# USB_Serial.net
KiCad netlist of a schematic drawn in EAGLE
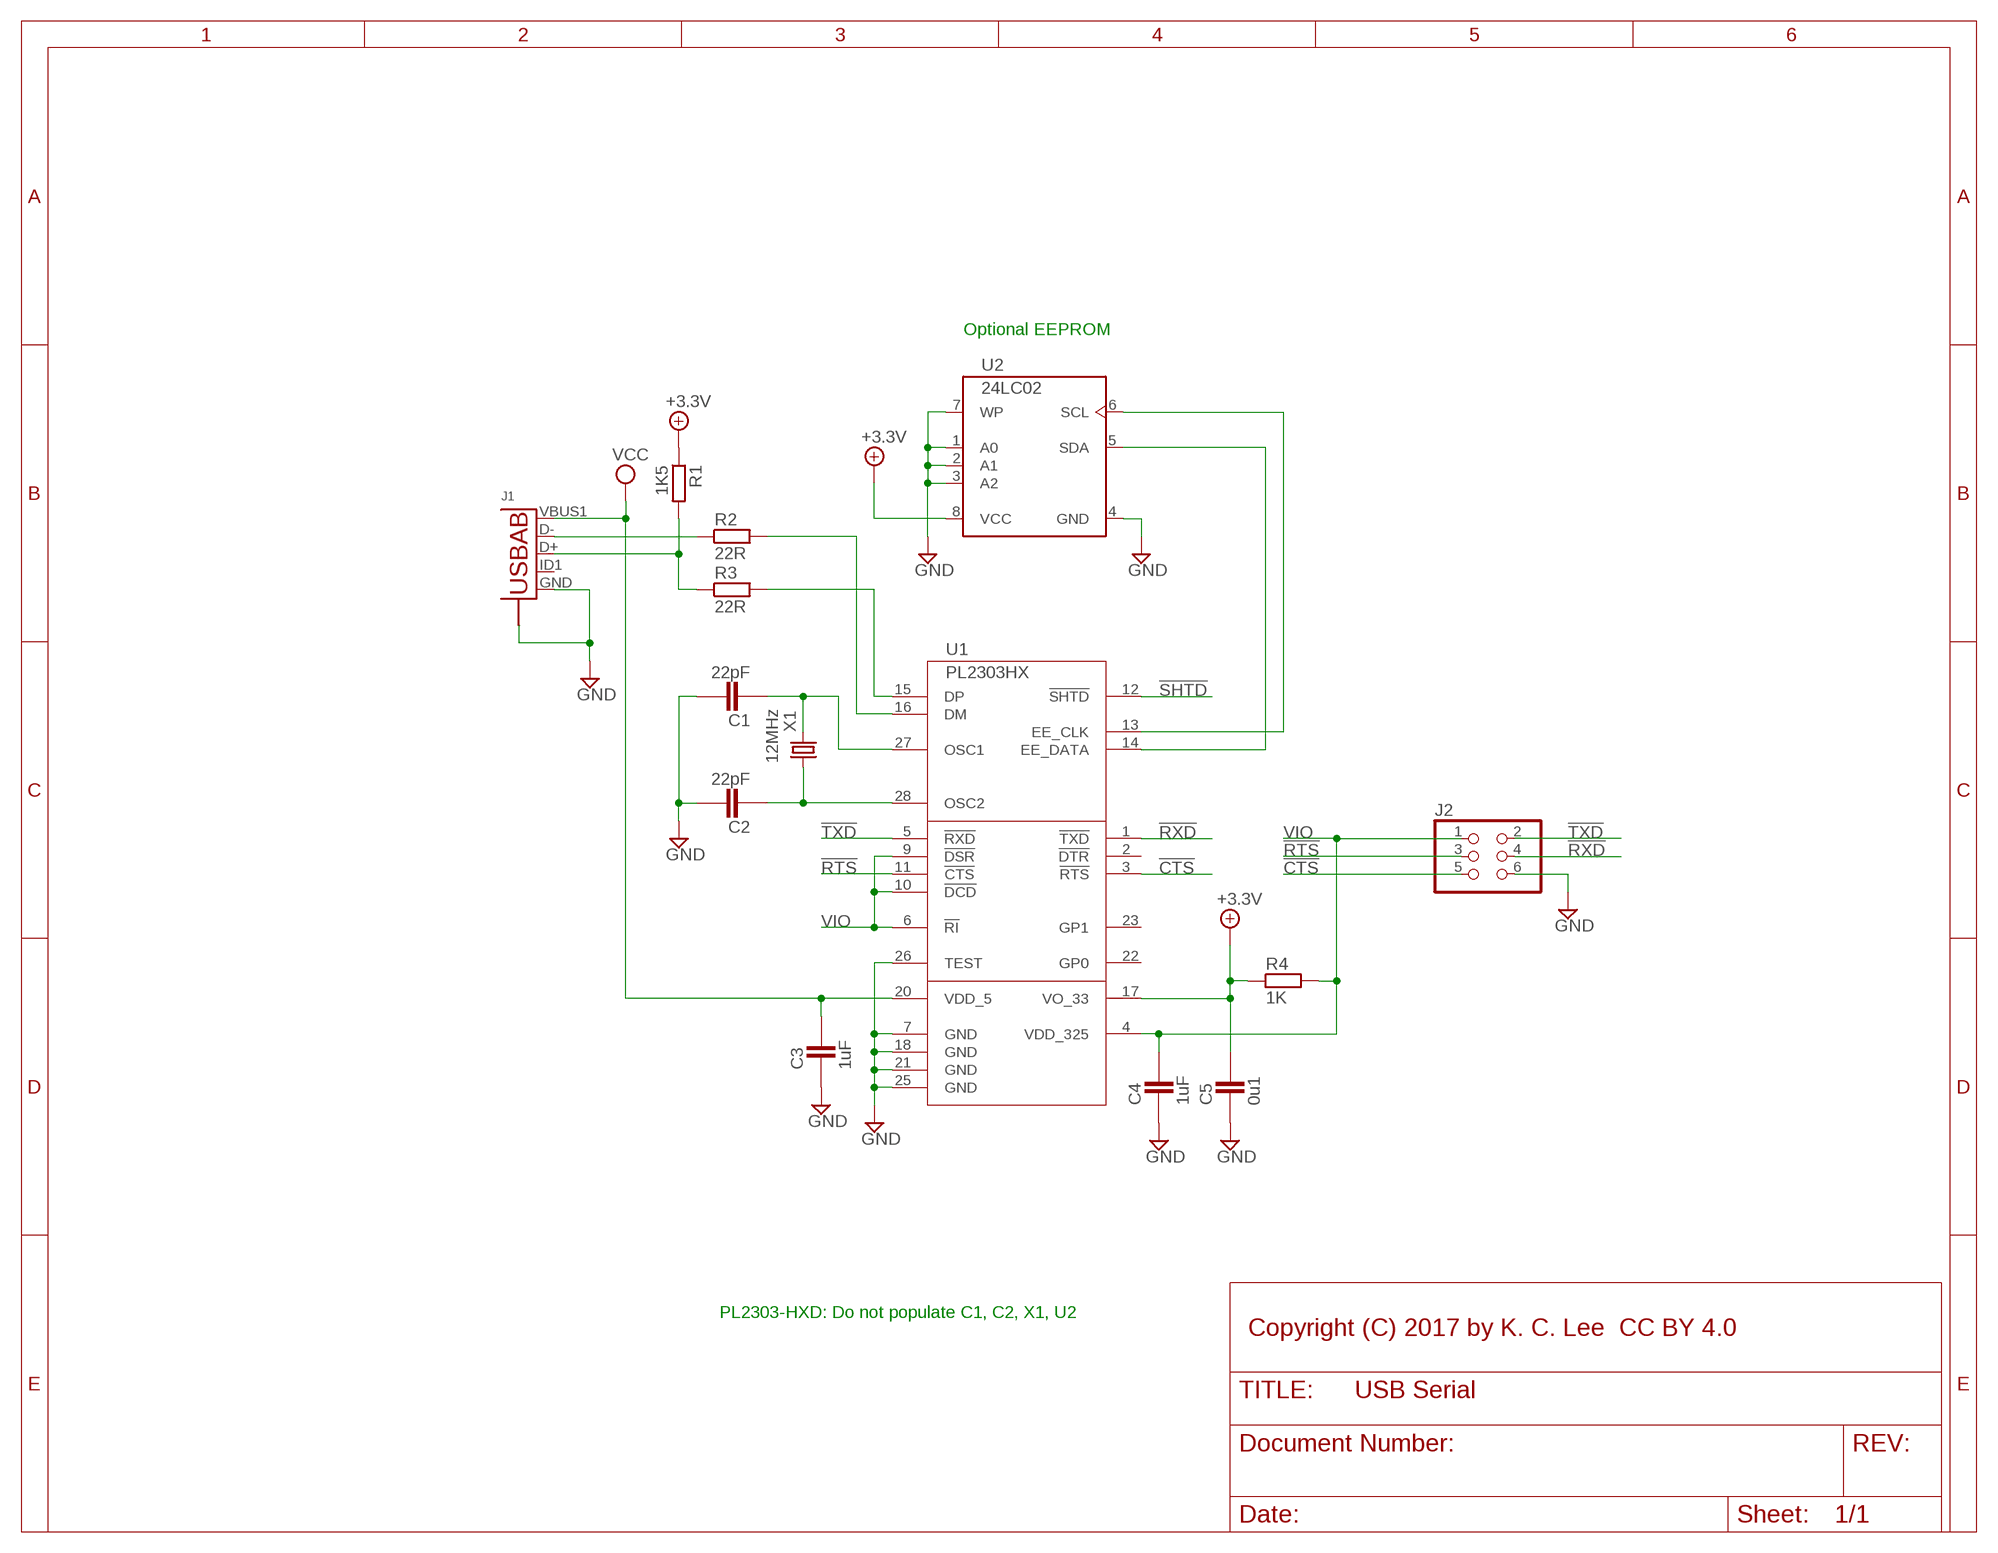
[diagram p0: schematic, sheet 1]

(export (version "E")
  (design (tool "Eeschema 10.0.6"))
  (components
    (comp (ref "C1")
      (value "22pF")
      (footprint "eagle-import:CAPC1608X92N")
      (fields (field (name "PARTNO") "22PF 0603"))
      (libsource (lib "eagle-import") (part "CAPACITOR_0603"))
    )
    (comp (ref "C2")
      (value "22pF")
      (footprint "eagle-import:CAPC1608X92N")
      (fields (field (name "PARTNO") "22PF 0603"))
      (libsource (lib "eagle-import") (part "CAPACITOR_0603"))
    )
    (comp (ref "C3")
      (value "1uF")
      (footprint "eagle-import:CAPC1608X92N")
      (fields (field (name "PARTNO") "1UF X7R 0603"))
      (libsource (lib "eagle-import") (part "CAPACITOR_0603"))
    )
    (comp (ref "C4")
      (value "1uF")
      (footprint "eagle-import:CAPC1608X92N")
      (fields (field (name "PARTNO") "1UF X7R 0603"))
      (libsource (lib "eagle-import") (part "CAPACITOR_0603"))
    )
    (comp (ref "C5")
      (value "0u1")
      (footprint "eagle-import:CAPC1608X92N")
      (fields (field (name "PARTNO") "0U1 X7R 0603"))
      (libsource (lib "eagle-import") (part "CAPACITOR_0603"))
    )
    (comp (ref "J1")
      (value "USB-ABBG-ORG")
      (footprint "eagle-import:USB-AB-MICRO-SMD_V03_SMT")
      (fields (field (name "PARTNO") "SMT MICRO USB FEMALE"))
      (libsource (lib "eagle-import") (part "USB-ABBG-ORG"))
    )
    (comp (ref "J2")
      (value "PINHD-2X3_2.00")
      (footprint "eagle-import:2X03M_TH")
      (fields (field (name "PARTNO") "3X2 HEADER 2MM THROUGH HOLE"))
      (libsource (lib "eagle-import") (part "PINHD-2X3_2.00"))
    )
    (comp (ref "R1")
      (value "1K5")
      (footprint "eagle-import:RESC1608X55N")
      (fields (field (name "PARTNO") "1K5 0603"))
      (libsource (lib "eagle-import") (part "RESISTOR_0603"))
    )
    (comp (ref "R2")
      (value "22R")
      (footprint "eagle-import:RESC1608X55N")
      (fields (field (name "PARTNO") "22R 0603"))
      (libsource (lib "eagle-import") (part "RESISTOR_0603"))
    )
    (comp (ref "R3")
      (value "22R")
      (footprint "eagle-import:RESC1608X55N")
      (fields (field (name "PARTNO") "22R 0603"))
      (libsource (lib "eagle-import") (part "RESISTOR_0603"))
    )
    (comp (ref "R4")
      (value "1K")
      (footprint "eagle-import:RESC1608X55N")
      (fields (field (name "PARTNO") "1K 0603"))
      (libsource (lib "eagle-import") (part "RESISTOR_0603"))
    )
    (comp (ref "U1")
      (value "PL2303HX")
      (footprint "eagle-import:SSOP28DB")
      (fields (field (name "PARTNO") "PL-2303HXD SSOP"))
      (libsource (lib "eagle-import") (part "PL2303HXASSOP"))
    )
    (comp (ref "U2")
      (value "24LC02")
      (footprint "eagle-import:TSSOP8")
      (libsource (lib "eagle-import") (part "24ST"))
    )
    (comp (ref "X1")
      (value "12MHz")
      (footprint "eagle-import:TC26H")
      (fields (field (name "PARTNO") "12MHZ TC26"))
      (libsource (lib "eagle-import") (part "CRYSTALTC26H"))
    )
  )
  (nets
    (net (code "1") (name "+3.3V") (class "Default")
      (node (ref "C5") (pin "2") (pinfunction "2_2") (pintype "passive"))
      (node (ref "R1") (pin "1") (pinfunction "1_1") (pintype "passive"))
      (node (ref "R4") (pin "1") (pinfunction "1_1") (pintype "passive"))
      (node (ref "U1") (pin "17") (pinfunction "VO_33_17") (pintype "output"))
      (node (ref "U2") (pin "8") (pinfunction "VCC_8") (pintype "power_in"))
    )
    (net (code "2") (name "/VIO") (class "Default")
      (node (ref "C4") (pin "2") (pinfunction "2_2") (pintype "passive"))
      (node (ref "J2") (pin "1") (pinfunction "1_1") (pintype "passive"))
      (node (ref "R4") (pin "2") (pinfunction "2_2") (pintype "passive"))
      (node (ref "U1") (pin "10") (pinfunction "~{DCD}_10") (pintype "bidirectional"))
      (node (ref "U1") (pin "4") (pinfunction "VDD_325_4") (pintype "input"))
      (node (ref "U1") (pin "6") (pinfunction "~{RI}_6") (pintype "bidirectional"))
      (node (ref "U1") (pin "9") (pinfunction "~{DSR}_9") (pintype "bidirectional"))
    )
    (net (code "3") (name "/~{CTS}") (class "Default")
      (node (ref "J2") (pin "5") (pinfunction "5_5") (pintype "passive"))
      (node (ref "U1") (pin "3") (pinfunction "~{RTS}_3") (pintype "output"))
    )
    (net (code "4") (name "/~{RTS}") (class "Default")
      (node (ref "J2") (pin "3") (pinfunction "3_3") (pintype "passive"))
      (node (ref "U1") (pin "11") (pinfunction "~{CTS}_11") (pintype "bidirectional"))
    )
    (net (code "5") (name "/~{RXD}") (class "Default")
      (node (ref "J2") (pin "4") (pinfunction "4_4") (pintype "passive"))
      (node (ref "U1") (pin "1") (pinfunction "~{TXD}_1") (pintype "output"))
    )
    (net (code "6") (name "/~{SHTD}") (class "Default")
      (node (ref "U1") (pin "12") (pinfunction "~{SHTD}_12") (pintype "output"))
    )
    (net (code "7") (name "/~{TXD}") (class "Default")
      (node (ref "J2") (pin "2") (pinfunction "2_2") (pintype "passive"))
      (node (ref "U1") (pin "5") (pinfunction "~{RXD}_5") (pintype "input"))
    )
    (net (code "8") (name "GND") (class "Default")
      (node (ref "C1") (pin "2") (pinfunction "2_2") (pintype "passive"))
      (node (ref "C2") (pin "2") (pinfunction "2_2") (pintype "passive"))
      (node (ref "C3") (pin "1") (pinfunction "1_1") (pintype "passive"))
      (node (ref "C4") (pin "1") (pinfunction "1_1") (pintype "passive"))
      (node (ref "C5") (pin "1") (pinfunction "1_1") (pintype "passive"))
      (node (ref "J1") (pin "GND") (pinfunction "GND_GND") (pintype "bidirectional"))
      (node (ref "J1") (pin "S1") (pinfunction "S_S1") (pintype "bidirectional"))
      (node (ref "J1") (pin "S2") (pinfunction "S_S2") (pintype "bidirectional"))
      (node (ref "J1") (pin "S3") (pinfunction "S_S3") (pintype "bidirectional"))
      (node (ref "J1") (pin "S4") (pinfunction "S_S4") (pintype "bidirectional"))
      (node (ref "J2") (pin "6") (pinfunction "6_6") (pintype "passive"))
      (node (ref "U1") (pin "18") (pinfunction "GND_18") (pintype "bidirectional"))
      (node (ref "U1") (pin "21") (pinfunction "GND_21") (pintype "bidirectional"))
      (node (ref "U1") (pin "25") (pinfunction "GND_25") (pintype "bidirectional"))
      (node (ref "U1") (pin "26") (pinfunction "TEST_26") (pintype "input"))
      (node (ref "U1") (pin "7") (pinfunction "GND_7") (pintype "input"))
      (node (ref "U2") (pin "1") (pinfunction "A0_1") (pintype "bidirectional"))
      (node (ref "U2") (pin "2") (pinfunction "A1_2") (pintype "bidirectional"))
      (node (ref "U2") (pin "3") (pinfunction "A2_3") (pintype "bidirectional"))
      (node (ref "U2") (pin "4") (pinfunction "GND_4") (pintype "power_in"))
      (node (ref "U2") (pin "7") (pinfunction "WP_7") (pintype "bidirectional"))
    )
    (net (code "9") (name "Net-(J1-PadD+)") (class "Default")
      (node (ref "J1") (pin "D+") (pinfunction "D+_D+") (pintype "bidirectional"))
      (node (ref "R1") (pin "2") (pinfunction "2_2") (pintype "passive"))
      (node (ref "R3") (pin "1") (pinfunction "1_1") (pintype "passive"))
    )
    (net (code "10") (name "Net-(J1-PadD-)") (class "Default")
      (node (ref "J1") (pin "D-") (pinfunction "D-_D-") (pintype "bidirectional"))
      (node (ref "R2") (pin "1") (pinfunction "1_1") (pintype "passive"))
    )
    (net (code "11") (name "Net-(U1-DM)") (class "Default")
      (node (ref "R2") (pin "2") (pinfunction "2_2") (pintype "passive"))
      (node (ref "U1") (pin "16") (pinfunction "DM_16") (pintype "bidirectional"))
    )
    (net (code "12") (name "Net-(U1-DP)") (class "Default")
      (node (ref "R3") (pin "2") (pinfunction "2_2") (pintype "passive"))
      (node (ref "U1") (pin "15") (pinfunction "DP_15") (pintype "bidirectional"))
    )
    (net (code "13") (name "Net-(U1-EE_CLK)") (class "Default")
      (node (ref "U1") (pin "13") (pinfunction "EE_CLK_13") (pintype "bidirectional"))
      (node (ref "U2") (pin "6") (pinfunction "SCL_6") (pintype "input"))
    )
    (net (code "14") (name "Net-(U1-EE_DATA)") (class "Default")
      (node (ref "U1") (pin "14") (pinfunction "EE_DATA_14") (pintype "bidirectional"))
      (node (ref "U2") (pin "5") (pinfunction "SDA_5") (pintype "bidirectional"))
    )
    (net (code "15") (name "Net-(U1-OSC1)") (class "Default")
      (node (ref "C1") (pin "1") (pinfunction "1_1") (pintype "passive"))
      (node (ref "U1") (pin "27") (pinfunction "OSC1_27") (pintype "input"))
      (node (ref "X1") (pin "2") (pinfunction "2_2") (pintype "passive"))
    )
    (net (code "16") (name "Net-(U1-OSC2)") (class "Default")
      (node (ref "C2") (pin "1") (pinfunction "1_1") (pintype "passive"))
      (node (ref "U1") (pin "28") (pinfunction "OSC2_28") (pintype "bidirectional"))
      (node (ref "X1") (pin "1") (pinfunction "1_1") (pintype "passive"))
    )
    (net (code "17") (name "VCC") (class "Default")
      (node (ref "C3") (pin "2") (pinfunction "2_2") (pintype "passive"))
      (node (ref "J1") (pin "VBUS1") (pinfunction "VBUS_VBUS1") (pintype "bidirectional"))
      (node (ref "U1") (pin "20") (pinfunction "VDD_5_20") (pintype "input"))
    )
    (net (code "18") (name "unconnected-(J1-USBID-PadID1)") (class "Default")
      (node (ref "J1") (pin "ID1") (pinfunction "USBID_ID1") (pintype "bidirectional"))
    )
    (net (code "19") (name "unconnected-(U1-GP0-Pad22)") (class "Default")
      (node (ref "U1") (pin "22") (pinfunction "GP0_22") (pintype "bidirectional"))
    )
    (net (code "20") (name "unconnected-(U1-GP1-Pad23)") (class "Default")
      (node (ref "U1") (pin "23") (pinfunction "GP1_23") (pintype "bidirectional"))
    )
    (net (code "21") (name "unconnected-(U1-~{DTR}-Pad2)") (class "Default")
      (node (ref "U1") (pin "2") (pinfunction "~{DTR}_2") (pintype "output"))
    )
  )
)
